# TPS65988.net
KiCad netlist of a schematic drawn in Altium Designer
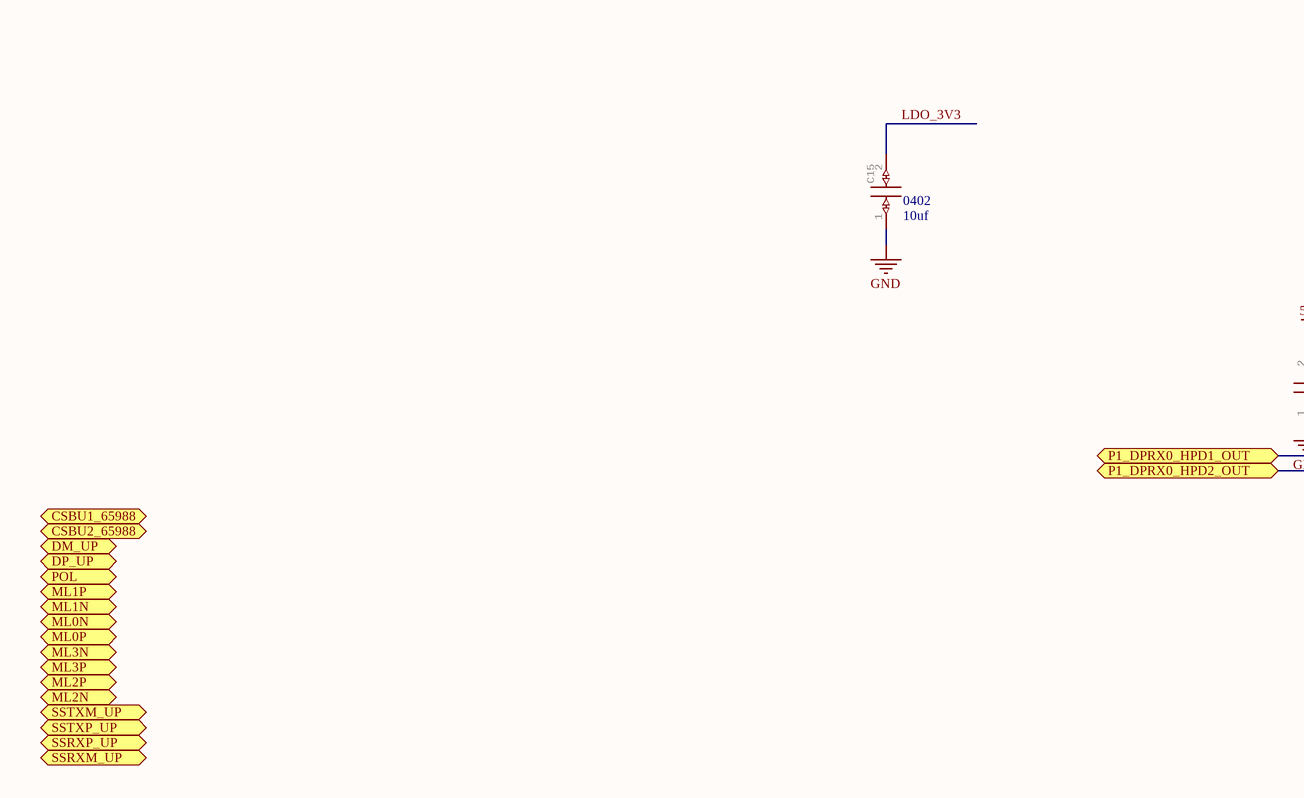
[diagram p0: TPS65988.SchDoc, left]
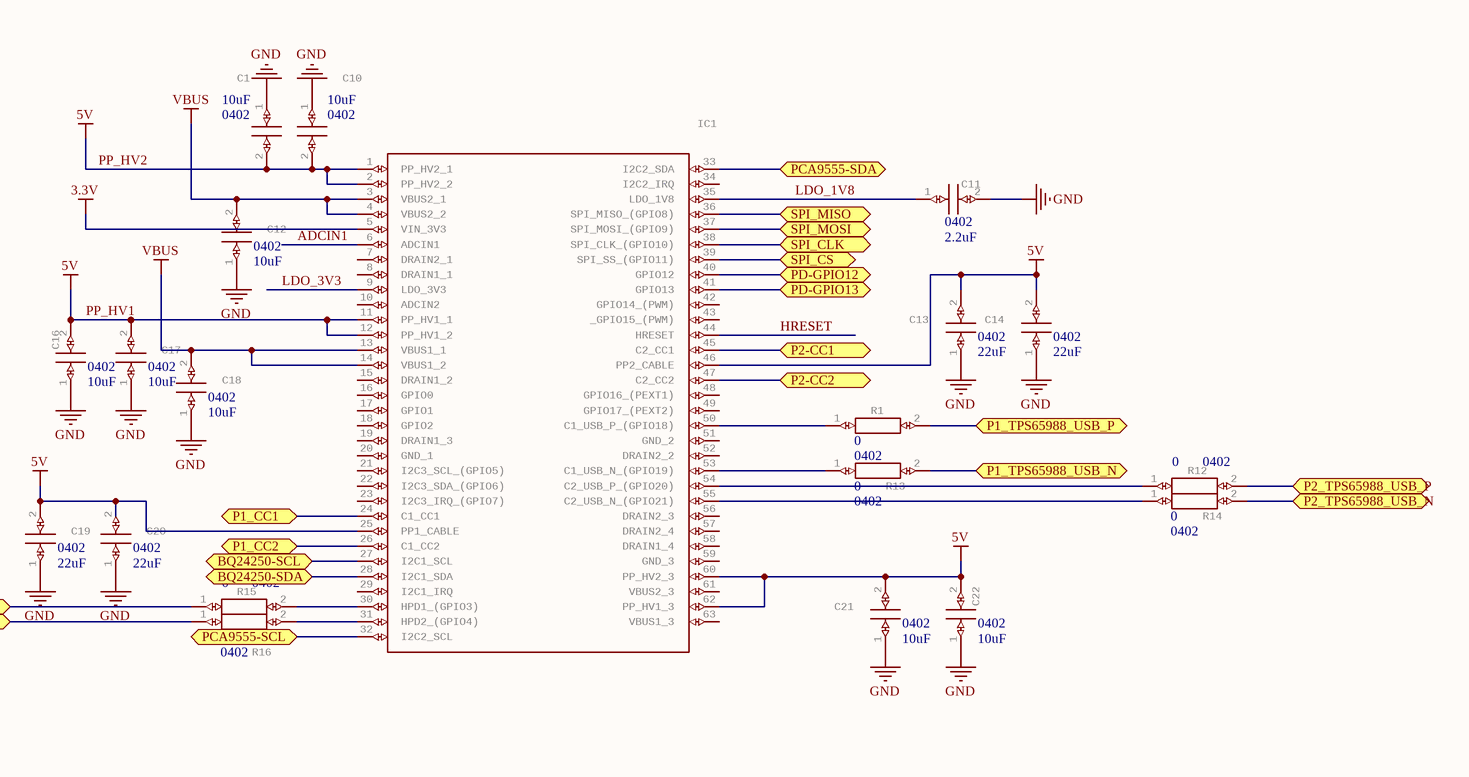
[diagram p1: TPS65988.SchDoc, right]

(export (version "E")
  (design (tool "Eeschema 10.0.6"))
  (components
    (comp (ref "C1")
      (value "10uF")
      (footprint "CAPC1005X56N")
      (fields
        (field (name "MANUFACTURER_PART_NUMBER") "04025C104KAT2A")
        (field (name "MOUSER_PART_NUMBER") "581-04025C104KAT2A")
        (field (name "PACKAGE") "0402")
        (field (name "Comment") "Multilayer Ceramic Capacitors MLCC - SMD/SMT 50V .1uF X7R 0402 10% Tol   Source:  Datasheet")
      )
      (libsource (lib "C0402-GP") (part "04025C104KAT2A"))
    )
    (comp (ref "C10")
      (value "10uF")
      (footprint "CAPC1005X56N")
      (fields
        (field (name "MANUFACTURER_PART_NUMBER") "04025C104KAT2A")
        (field (name "MOUSER_PART_NUMBER") "581-04025C104KAT2A")
        (field (name "PACKAGE") "0402")
        (field (name "Comment") "Multilayer Ceramic Capacitors MLCC - SMD/SMT 50V .1uF X7R 0402 10% Tol   Source:  Datasheet")
      )
      (libsource (lib "C0402-GP") (part "04025C104KAT2A"))
    )
    (comp (ref "C11")
      (value "2.2uF")
      (footprint "CAPC1005X56N")
      (fields
        (field (name "MANUFACTURER_PART_NUMBER") "04025C104KAT2A")
        (field (name "MOUSER_PART_NUMBER") "581-04025C104KAT2A")
        (field (name "PACKAGE") "0402")
        (field (name "Comment") "Multilayer Ceramic Capacitors MLCC - SMD/SMT 50V .1uF X7R 0402 10% Tol   Source:  Datasheet")
      )
      (libsource (lib "C0402-GP") (part "04025C104KAT2A"))
    )
    (comp (ref "C12")
      (value "10uF")
      (footprint "CAPC1005X56N")
      (fields
        (field (name "MANUFACTURER_PART_NUMBER") "04025C104KAT2A")
        (field (name "MOUSER_PART_NUMBER") "581-04025C104KAT2A")
        (field (name "PACKAGE") "0402")
        (field (name "Comment") "Multilayer Ceramic Capacitors MLCC - SMD/SMT 50V .1uF X7R 0402 10% Tol   Source:  Datasheet")
      )
      (libsource (lib "C0402-GP") (part "04025C104KAT2A"))
    )
    (comp (ref "C13")
      (value "22uF")
      (footprint "CAPC1005X56N")
      (fields
        (field (name "MANUFACTURER_PART_NUMBER") "04025C104KAT2A")
        (field (name "MOUSER_PART_NUMBER") "581-04025C104KAT2A")
        (field (name "PACKAGE") "0402")
        (field (name "Comment") "Multilayer Ceramic Capacitors MLCC - SMD/SMT 50V .1uF X7R 0402 10% Tol   Source:  Datasheet")
      )
      (libsource (lib "C0402-GP") (part "04025C104KAT2A"))
    )
    (comp (ref "C14")
      (value "22uF")
      (footprint "CAPC1005X56N")
      (fields
        (field (name "MANUFACTURER_PART_NUMBER") "04025C104KAT2A")
        (field (name "MOUSER_PART_NUMBER") "581-04025C104KAT2A")
        (field (name "PACKAGE") "0402")
        (field (name "Comment") "Multilayer Ceramic Capacitors MLCC - SMD/SMT 50V .1uF X7R 0402 10% Tol   Source:  Datasheet")
      )
      (libsource (lib "C0402-GP") (part "04025C104KAT2A"))
    )
    (comp (ref "C15")
      (value "10uf")
      (footprint "CAPC1005X56N")
      (fields
        (field (name "MANUFACTURER_PART_NUMBER") "04025C104KAT2A")
        (field (name "MOUSER_PART_NUMBER") "581-04025C104KAT2A")
        (field (name "PACKAGE") "0402")
        (field (name "Comment") "Multilayer Ceramic Capacitors MLCC - SMD/SMT 50V .1uF X7R 0402 10% Tol   Source:  Datasheet")
      )
      (libsource (lib "C0402-GP") (part "04025C104KAT2A"))
    )
    (comp (ref "C16")
      (value "10uF")
      (footprint "CAPC1005X56N")
      (fields
        (field (name "MANUFACTURER_PART_NUMBER") "04025C104KAT2A")
        (field (name "MOUSER_PART_NUMBER") "581-04025C104KAT2A")
        (field (name "PACKAGE") "0402")
        (field (name "Comment") "Multilayer Ceramic Capacitors MLCC - SMD/SMT 50V .1uF X7R 0402 10% Tol   Source:  Datasheet")
      )
      (libsource (lib "C0402-GP") (part "04025C104KAT2A"))
    )
    (comp (ref "C17")
      (value "10uF")
      (footprint "CAPC1005X56N")
      (fields
        (field (name "MANUFACTURER_PART_NUMBER") "04025C104KAT2A")
        (field (name "MOUSER_PART_NUMBER") "581-04025C104KAT2A")
        (field (name "PACKAGE") "0402")
        (field (name "Comment") "Multilayer Ceramic Capacitors MLCC - SMD/SMT 50V .1uF X7R 0402 10% Tol   Source:  Datasheet")
      )
      (libsource (lib "C0402-GP") (part "04025C104KAT2A"))
    )
    (comp (ref "C18")
      (value "10uF")
      (footprint "CAPC1005X56N")
      (fields
        (field (name "MANUFACTURER_PART_NUMBER") "04025C104KAT2A")
        (field (name "MOUSER_PART_NUMBER") "581-04025C104KAT2A")
        (field (name "PACKAGE") "0402")
        (field (name "Comment") "Multilayer Ceramic Capacitors MLCC - SMD/SMT 50V .1uF X7R 0402 10% Tol   Source:  Datasheet")
      )
      (libsource (lib "C0402-GP") (part "04025C104KAT2A"))
    )
    (comp (ref "C19")
      (value "22uF")
      (footprint "CAPC1005X56N")
      (fields
        (field (name "MANUFACTURER_PART_NUMBER") "04025C104KAT2A")
        (field (name "MOUSER_PART_NUMBER") "581-04025C104KAT2A")
        (field (name "PACKAGE") "0402")
        (field (name "Comment") "Multilayer Ceramic Capacitors MLCC - SMD/SMT 50V .1uF X7R 0402 10% Tol   Source:  Datasheet")
      )
      (libsource (lib "C0402-GP") (part "04025C104KAT2A"))
    )
    (comp (ref "C20")
      (value "22uF")
      (footprint "CAPC1005X56N")
      (fields
        (field (name "MANUFACTURER_PART_NUMBER") "04025C104KAT2A")
        (field (name "MOUSER_PART_NUMBER") "581-04025C104KAT2A")
        (field (name "PACKAGE") "0402")
        (field (name "Comment") "Multilayer Ceramic Capacitors MLCC - SMD/SMT 50V .1uF X7R 0402 10% Tol   Source:  Datasheet")
      )
      (libsource (lib "C0402-GP") (part "04025C104KAT2A"))
    )
    (comp (ref "C21")
      (value "10uF")
      (footprint "CAPC1005X56N")
      (fields
        (field (name "MANUFACTURER_PART_NUMBER") "04025C104KAT2A")
        (field (name "MOUSER_PART_NUMBER") "581-04025C104KAT2A")
        (field (name "PACKAGE") "0402")
        (field (name "Comment") "Multilayer Ceramic Capacitors MLCC - SMD/SMT 50V .1uF X7R 0402 10% Tol   Source:  Datasheet")
      )
      (libsource (lib "C0402-GP") (part "04025C104KAT2A"))
    )
    (comp (ref "C22")
      (value "10uF")
      (footprint "CAPC1005X56N")
      (fields
        (field (name "MANUFACTURER_PART_NUMBER") "04025C104KAT2A")
        (field (name "MOUSER_PART_NUMBER") "581-04025C104KAT2A")
        (field (name "PACKAGE") "0402")
        (field (name "Comment") "Multilayer Ceramic Capacitors MLCC - SMD/SMT 50V .1uF X7R 0402 10% Tol   Source:  Datasheet")
      )
      (libsource (lib "C0402-GP") (part "04025C104KAT2A"))
    )
    (comp (ref "IC1")
      (value "Dual port USB Type-C and PD Controller with integrated power switches for PC & Thunderbolt systems   Source:  Datasheet")
      (footprint "TPS65988DJRSHR")
      (fields
        (field (name "MANUFACTURER_PART_NUMBER") "TPS65988DJRSHR")
        (field (name "MOUSER_PART_NUMBER") "595-TPS65988DJRSHR")
      )
      (libsource (lib "TPS65988DJRSHR") (part "TPS65988DJRSHR"))
    )
    (comp (ref "R1")
      (value "0")
      (footprint "RESC1005X40N")
      (fields
        (field (name "MANUFACTURER_PART_NUMBER") "RC0402FR-071KL")
        (field (name "MOUSER_PART_NUMBER") "603-RC0402FR-071KL")
        (field (name "PACKAGE") "0402")
        (field (name "Comment") "GENERAL PURPOSE CHIP RESISTORS   Source:  Datasheet")
      )
      (libsource (lib "R0402-GP") (part "RC0402FR-071KL"))
    )
    (comp (ref "R12")
      (value "0")
      (footprint "RESC1005X40N")
      (fields
        (field (name "MANUFACTURER_PART_NUMBER") "RC0402FR-071KL")
        (field (name "MOUSER_PART_NUMBER") "603-RC0402FR-071KL")
        (field (name "PACKAGE") "0402")
        (field (name "Comment") "GENERAL PURPOSE CHIP RESISTORS   Source:  Datasheet")
      )
      (libsource (lib "R0402-GP") (part "RC0402FR-071KL"))
    )
    (comp (ref "R13")
      (value "0")
      (footprint "RESC1005X40N")
      (fields
        (field (name "MANUFACTURER_PART_NUMBER") "RC0402FR-071KL")
        (field (name "MOUSER_PART_NUMBER") "603-RC0402FR-071KL")
        (field (name "PACKAGE") "0402")
        (field (name "Comment") "GENERAL PURPOSE CHIP RESISTORS   Source:  Datasheet")
      )
      (libsource (lib "R0402-GP") (part "RC0402FR-071KL"))
    )
    (comp (ref "R14")
      (value "0")
      (footprint "RESC1005X40N")
      (fields
        (field (name "MANUFACTURER_PART_NUMBER") "RC0402FR-071KL")
        (field (name "MOUSER_PART_NUMBER") "603-RC0402FR-071KL")
        (field (name "PACKAGE") "0402")
        (field (name "Comment") "GENERAL PURPOSE CHIP RESISTORS   Source:  Datasheet")
      )
      (libsource (lib "R0402-GP") (part "RC0402FR-071KL"))
    )
    (comp (ref "R15")
      (value "0")
      (footprint "RESC1005X40N")
      (fields
        (field (name "MANUFACTURER_PART_NUMBER") "RC0402FR-071KL")
        (field (name "MOUSER_PART_NUMBER") "603-RC0402FR-071KL")
        (field (name "PACKAGE") "0402")
        (field (name "Comment") "GENERAL PURPOSE CHIP RESISTORS   Source:  Datasheet")
      )
      (libsource (lib "R0402-GP") (part "RC0402FR-071KL"))
    )
    (comp (ref "R16")
      (value "0")
      (footprint "RESC1005X40N")
      (fields
        (field (name "MANUFACTURER_PART_NUMBER") "RC0402FR-071KL")
        (field (name "MOUSER_PART_NUMBER") "603-RC0402FR-071KL")
        (field (name "PACKAGE") "0402")
        (field (name "Comment") "GENERAL PURPOSE CHIP RESISTORS   Source:  Datasheet")
      )
      (libsource (lib "R0402-GP") (part "RC0402FR-071KL"))
    )
  )
  (nets
    (net (code "1") (name "/ADCIN1") (class "Default")
      (node (ref "IC1") (pin "6") (pinfunction "ADCIN1_6") (pintype "bidirectional"))
    )
    (net (code "2") (name "/BQ24250-SCL") (class "Default")
      (node (ref "IC1") (pin "27") (pinfunction "I2C1_SCL_27") (pintype "bidirectional"))
    )
    (net (code "3") (name "/BQ24250-SDA") (class "Default")
      (node (ref "IC1") (pin "28") (pinfunction "I2C1_SDA_28") (pintype "bidirectional"))
    )
    (net (code "8") (name "/HRESET") (class "Default")
      (node (ref "IC1") (pin "44") (pinfunction "HRESET_44") (pintype "bidirectional"))
    )
    (net (code "9") (name "/LDO_1V8") (class "Default")
      (node (ref "C11") (pin "1") (pinfunction "1_1") (pintype "bidirectional"))
      (node (ref "IC1") (pin "35") (pinfunction "LDO_1V8_35") (pintype "bidirectional"))
    )
    (net (code "10") (name "/LDO_3V3") (class "Default")
      (node (ref "C15") (pin "2") (pinfunction "2_2") (pintype "bidirectional"))
      (node (ref "IC1") (pin "9") (pinfunction "LDO_3V3_9") (pintype "bidirectional"))
    )
    (net (code "19") (name "/P1_CC1") (class "Default")
      (node (ref "IC1") (pin "24") (pinfunction "C1_CC1_24") (pintype "bidirectional"))
    )
    (net (code "20") (name "/P1_CC2") (class "Default")
      (node (ref "IC1") (pin "26") (pinfunction "C1_CC2_26") (pintype "bidirectional"))
    )
    (net (code "21") (name "/P1_DPRX0_HPD1_OUT") (class "Default")
      (node (ref "R15") (pin "1") (pinfunction "1_1") (pintype "bidirectional"))
    )
    (net (code "22") (name "/P1_DPRX0_HPD2_OUT") (class "Default")
      (node (ref "R16") (pin "1") (pinfunction "1_1") (pintype "bidirectional"))
    )
    (net (code "23") (name "/P1_TPS65988_USB_N") (class "Default")
      (node (ref "R13") (pin "2") (pinfunction "2_2") (pintype "bidirectional"))
    )
    (net (code "24") (name "/P1_TPS65988_USB_P") (class "Default")
      (node (ref "R1") (pin "2") (pinfunction "2_2") (pintype "bidirectional"))
    )
    (net (code "25") (name "/P2-CC1") (class "Default")
      (node (ref "IC1") (pin "45") (pinfunction "C2_CC1_45") (pintype "bidirectional"))
    )
    (net (code "26") (name "/P2-CC2") (class "Default")
      (node (ref "IC1") (pin "47") (pinfunction "C2_CC2_47") (pintype "bidirectional"))
    )
    (net (code "27") (name "/P2_TPS65988_USB_N") (class "Default")
      (node (ref "R14") (pin "2") (pinfunction "2_2") (pintype "bidirectional"))
    )
    (net (code "28") (name "/P2_TPS65988_USB_P") (class "Default")
      (node (ref "R12") (pin "2") (pinfunction "2_2") (pintype "bidirectional"))
    )
    (net (code "29") (name "/PCA9555-SCL") (class "Default")
      (node (ref "IC1") (pin "32") (pinfunction "I2C2_SCL_32") (pintype "bidirectional"))
    )
    (net (code "30") (name "/PCA9555-SDA") (class "Default")
      (node (ref "IC1") (pin "33") (pinfunction "I2C2_SDA_33") (pintype "bidirectional"))
    )
    (net (code "31") (name "/PD-GPIO12") (class "Default")
      (node (ref "IC1") (pin "40") (pinfunction "GPIO12_40") (pintype "bidirectional"))
    )
    (net (code "32") (name "/PD-GPIO13") (class "Default")
      (node (ref "IC1") (pin "41") (pinfunction "GPIO13_41") (pintype "bidirectional"))
    )
    (net (code "34") (name "/SPI_CLK") (class "Default")
      (node (ref "IC1") (pin "38") (pinfunction "SPI_CLK_(GPIO10)_38") (pintype "bidirectional"))
    )
    (net (code "35") (name "/SPI_CS") (class "Default")
      (node (ref "IC1") (pin "39") (pinfunction "SPI_SS_(GPIO11)_39") (pintype "bidirectional"))
    )
    (net (code "36") (name "/SPI_MISO") (class "Default")
      (node (ref "IC1") (pin "36") (pinfunction "SPI_MISO_(GPIO8)_36") (pintype "bidirectional"))
    )
    (net (code "37") (name "/SPI_MOSI") (class "Default")
      (node (ref "IC1") (pin "37") (pinfunction "SPI_MOSI_(GPIO9)_37") (pintype "bidirectional"))
    )
    (net (code "42") (name "3.3V") (class "Default")
      (node (ref "IC1") (pin "5") (pinfunction "VIN_3V3_5") (pintype "bidirectional"))
    )
    (net (code "43") (name "5V") (class "Default")
      (node (ref "C1") (pin "2") (pinfunction "2_2") (pintype "bidirectional"))
      (node (ref "C10") (pin "2") (pinfunction "2_2") (pintype "bidirectional"))
      (node (ref "C13") (pin "2") (pinfunction "2_2") (pintype "bidirectional"))
      (node (ref "C14") (pin "2") (pinfunction "2_2") (pintype "bidirectional"))
      (node (ref "C16") (pin "2") (pinfunction "2_2") (pintype "bidirectional"))
      (node (ref "C17") (pin "2") (pinfunction "2_2") (pintype "bidirectional"))
      (node (ref "C19") (pin "2") (pinfunction "2_2") (pintype "bidirectional"))
      (node (ref "C20") (pin "2") (pinfunction "2_2") (pintype "bidirectional"))
      (node (ref "C21") (pin "2") (pinfunction "2_2") (pintype "bidirectional"))
      (node (ref "C22") (pin "2") (pinfunction "2_2") (pintype "bidirectional"))
      (node (ref "IC1") (pin "1") (pinfunction "PP_HV2_1_1") (pintype "bidirectional"))
      (node (ref "IC1") (pin "11") (pinfunction "PP_HV1_1_11") (pintype "bidirectional"))
      (node (ref "IC1") (pin "12") (pinfunction "PP_HV1_2_12") (pintype "bidirectional"))
      (node (ref "IC1") (pin "2") (pinfunction "PP_HV2_2_2") (pintype "bidirectional"))
      (node (ref "IC1") (pin "25") (pinfunction "PP1_CABLE_25") (pintype "bidirectional"))
      (node (ref "IC1") (pin "46") (pinfunction "PP2_CABLE_46") (pintype "bidirectional"))
      (node (ref "IC1") (pin "60") (pinfunction "PP_HV2_3_60") (pintype "bidirectional"))
      (node (ref "IC1") (pin "62") (pinfunction "PP_HV1_3_62") (pintype "bidirectional"))
    )
    (net (code "44") (name "GND") (class "Default")
      (node (ref "C1") (pin "1") (pinfunction "1_1") (pintype "bidirectional"))
      (node (ref "C10") (pin "1") (pinfunction "1_1") (pintype "bidirectional"))
      (node (ref "C11") (pin "2") (pinfunction "2_2") (pintype "bidirectional"))
      (node (ref "C12") (pin "1") (pinfunction "1_1") (pintype "bidirectional"))
      (node (ref "C13") (pin "1") (pinfunction "1_1") (pintype "bidirectional"))
      (node (ref "C14") (pin "1") (pinfunction "1_1") (pintype "bidirectional"))
      (node (ref "C15") (pin "1") (pinfunction "1_1") (pintype "bidirectional"))
      (node (ref "C16") (pin "1") (pinfunction "1_1") (pintype "bidirectional"))
      (node (ref "C17") (pin "1") (pinfunction "1_1") (pintype "bidirectional"))
      (node (ref "C18") (pin "1") (pinfunction "1_1") (pintype "bidirectional"))
      (node (ref "C19") (pin "1") (pinfunction "1_1") (pintype "bidirectional"))
      (node (ref "C20") (pin "1") (pinfunction "1_1") (pintype "bidirectional"))
      (node (ref "C21") (pin "1") (pinfunction "1_1") (pintype "bidirectional"))
      (node (ref "C22") (pin "1") (pinfunction "1_1") (pintype "bidirectional"))
    )
    (net (code "45") (name "Net-(IC1-C1_USB_N_(GPIO19))") (class "Default")
      (node (ref "IC1") (pin "53") (pinfunction "C1_USB_N_(GPIO19)_53") (pintype "bidirectional"))
      (node (ref "R13") (pin "1") (pinfunction "1_1") (pintype "bidirectional"))
    )
    (net (code "46") (name "Net-(IC1-C1_USB_P_(GPIO18))") (class "Default")
      (node (ref "IC1") (pin "50") (pinfunction "C1_USB_P_(GPIO18)_50") (pintype "bidirectional"))
      (node (ref "R1") (pin "1") (pinfunction "1_1") (pintype "bidirectional"))
    )
    (net (code "47") (name "Net-(IC1-C2_USB_N_(GPIO21))") (class "Default")
      (node (ref "IC1") (pin "55") (pinfunction "C2_USB_N_(GPIO21)_55") (pintype "bidirectional"))
      (node (ref "R14") (pin "1") (pinfunction "1_1") (pintype "bidirectional"))
    )
    (net (code "48") (name "Net-(IC1-C2_USB_P_(GPIO20))") (class "Default")
      (node (ref "IC1") (pin "54") (pinfunction "C2_USB_P_(GPIO20)_54") (pintype "bidirectional"))
      (node (ref "R12") (pin "1") (pinfunction "1_1") (pintype "bidirectional"))
    )
    (net (code "49") (name "Net-(IC1-HPD1_(GPIO3))") (class "Default")
      (node (ref "IC1") (pin "30") (pinfunction "HPD1_(GPIO3)_30") (pintype "bidirectional"))
      (node (ref "R15") (pin "2") (pinfunction "2_2") (pintype "bidirectional"))
    )
    (net (code "50") (name "Net-(IC1-HPD2_(GPIO4))") (class "Default")
      (node (ref "IC1") (pin "31") (pinfunction "HPD2_(GPIO4)_31") (pintype "bidirectional"))
      (node (ref "R16") (pin "2") (pinfunction "2_2") (pintype "bidirectional"))
    )
    (net (code "51") (name "VBUS") (class "Default")
      (node (ref "C12") (pin "2") (pinfunction "2_2") (pintype "bidirectional"))
      (node (ref "C18") (pin "2") (pinfunction "2_2") (pintype "bidirectional"))
      (node (ref "IC1") (pin "13") (pinfunction "VBUS1_1_13") (pintype "bidirectional"))
      (node (ref "IC1") (pin "14") (pinfunction "VBUS1_2_14") (pintype "bidirectional"))
      (node (ref "IC1") (pin "3") (pinfunction "VBUS2_1_3") (pintype "bidirectional"))
      (node (ref "IC1") (pin "4") (pinfunction "VBUS2_2_4") (pintype "bidirectional"))
    )
    (net (code "52") (name "unconnected-(IC1-ADCIN2-Pad10)") (class "Default")
      (node (ref "IC1") (pin "10") (pinfunction "ADCIN2_10") (pintype "bidirectional"))
    )
    (net (code "53") (name "unconnected-(IC1-DRAIN1_1-Pad8)") (class "Default")
      (node (ref "IC1") (pin "8") (pinfunction "DRAIN1_1_8") (pintype "bidirectional"))
    )
    (net (code "54") (name "unconnected-(IC1-DRAIN1_2-Pad15)") (class "Default")
      (node (ref "IC1") (pin "15") (pinfunction "DRAIN1_2_15") (pintype "bidirectional"))
    )
    (net (code "55") (name "unconnected-(IC1-DRAIN1_3-Pad19)") (class "Default")
      (node (ref "IC1") (pin "19") (pinfunction "DRAIN1_3_19") (pintype "bidirectional"))
    )
    (net (code "56") (name "unconnected-(IC1-DRAIN1_4-Pad58)") (class "Default")
      (node (ref "IC1") (pin "58") (pinfunction "DRAIN1_4_58") (pintype "bidirectional"))
    )
    (net (code "57") (name "unconnected-(IC1-DRAIN2_1-Pad7)") (class "Default")
      (node (ref "IC1") (pin "7") (pinfunction "DRAIN2_1_7") (pintype "bidirectional"))
    )
    (net (code "58") (name "unconnected-(IC1-DRAIN2_2-Pad52)") (class "Default")
      (node (ref "IC1") (pin "52") (pinfunction "DRAIN2_2_52") (pintype "bidirectional"))
    )
    (net (code "59") (name "unconnected-(IC1-DRAIN2_3-Pad56)") (class "Default")
      (node (ref "IC1") (pin "56") (pinfunction "DRAIN2_3_56") (pintype "bidirectional"))
    )
    (net (code "60") (name "unconnected-(IC1-DRAIN2_4-Pad57)") (class "Default")
      (node (ref "IC1") (pin "57") (pinfunction "DRAIN2_4_57") (pintype "bidirectional"))
    )
    (net (code "61") (name "unconnected-(IC1-GND_1-Pad20)") (class "Default")
      (node (ref "IC1") (pin "20") (pinfunction "GND_1_20") (pintype "bidirectional"))
    )
    (net (code "62") (name "unconnected-(IC1-GND_2-Pad51)") (class "Default")
      (node (ref "IC1") (pin "51") (pinfunction "GND_2_51") (pintype "bidirectional"))
    )
    (net (code "63") (name "unconnected-(IC1-GND_3-Pad59)") (class "Default")
      (node (ref "IC1") (pin "59") (pinfunction "GND_3_59") (pintype "bidirectional"))
    )
    (net (code "64") (name "unconnected-(IC1-GPIO0-Pad16)") (class "Default")
      (node (ref "IC1") (pin "16") (pinfunction "GPIO0_16") (pintype "bidirectional"))
    )
    (net (code "65") (name "unconnected-(IC1-GPIO1-Pad17)") (class "Default")
      (node (ref "IC1") (pin "17") (pinfunction "GPIO1_17") (pintype "bidirectional"))
    )
    (net (code "66") (name "unconnected-(IC1-GPIO2-Pad18)") (class "Default")
      (node (ref "IC1") (pin "18") (pinfunction "GPIO2_18") (pintype "bidirectional"))
    )
    (net (code "67") (name "unconnected-(IC1-GPIO14_(PWM)-Pad42)") (class "Default")
      (node (ref "IC1") (pin "42") (pinfunction "GPIO14_(PWM)_42") (pintype "bidirectional"))
    )
    (net (code "68") (name "unconnected-(IC1-GPIO16_(PEXT1)-Pad48)") (class "Default")
      (node (ref "IC1") (pin "48") (pinfunction "GPIO16_(PEXT1)_48") (pintype "bidirectional"))
    )
    (net (code "69") (name "unconnected-(IC1-GPIO17_(PEXT2)-Pad49)") (class "Default")
      (node (ref "IC1") (pin "49") (pinfunction "GPIO17_(PEXT2)_49") (pintype "bidirectional"))
    )
    (net (code "70") (name "unconnected-(IC1-I2C1_IRQ-Pad29)") (class "Default")
      (node (ref "IC1") (pin "29") (pinfunction "I2C1_IRQ_29") (pintype "bidirectional"))
    )
    (net (code "71") (name "unconnected-(IC1-I2C2_IRQ-Pad34)") (class "Default")
      (node (ref "IC1") (pin "34") (pinfunction "I2C2_IRQ_34") (pintype "bidirectional"))
    )
    (net (code "72") (name "unconnected-(IC1-I2C3_IRQ_(GPIO7)-Pad23)") (class "Default")
      (node (ref "IC1") (pin "23") (pinfunction "I2C3_IRQ_(GPIO7)_23") (pintype "bidirectional"))
    )
    (net (code "73") (name "unconnected-(IC1-I2C3_SCL_(GPIO5)-Pad21)") (class "Default")
      (node (ref "IC1") (pin "21") (pinfunction "I2C3_SCL_(GPIO5)_21") (pintype "bidirectional"))
    )
    (net (code "74") (name "unconnected-(IC1-I2C3_SDA_(GPIO6)-Pad22)") (class "Default")
      (node (ref "IC1") (pin "22") (pinfunction "I2C3_SDA_(GPIO6)_22") (pintype "bidirectional"))
    )
    (net (code "75") (name "unconnected-(IC1-VBUS1_3-Pad63)") (class "Default")
      (node (ref "IC1") (pin "63") (pinfunction "VBUS1_3_63") (pintype "bidirectional"))
    )
    (net (code "76") (name "unconnected-(IC1-VBUS2_3-Pad61)") (class "Default")
      (node (ref "IC1") (pin "61") (pinfunction "VBUS2_3_61") (pintype "bidirectional"))
    )
    (net (code "77") (name "unconnected-(IC1-_GPIO15_(PWM)-Pad43)") (class "Default")
      (node (ref "IC1") (pin "43") (pinfunction "_GPIO15_(PWM)_43") (pintype "bidirectional"))
    )
  )
)
